# MotorCell.net
KiCad netlist of a schematic drawn in Altium Designer
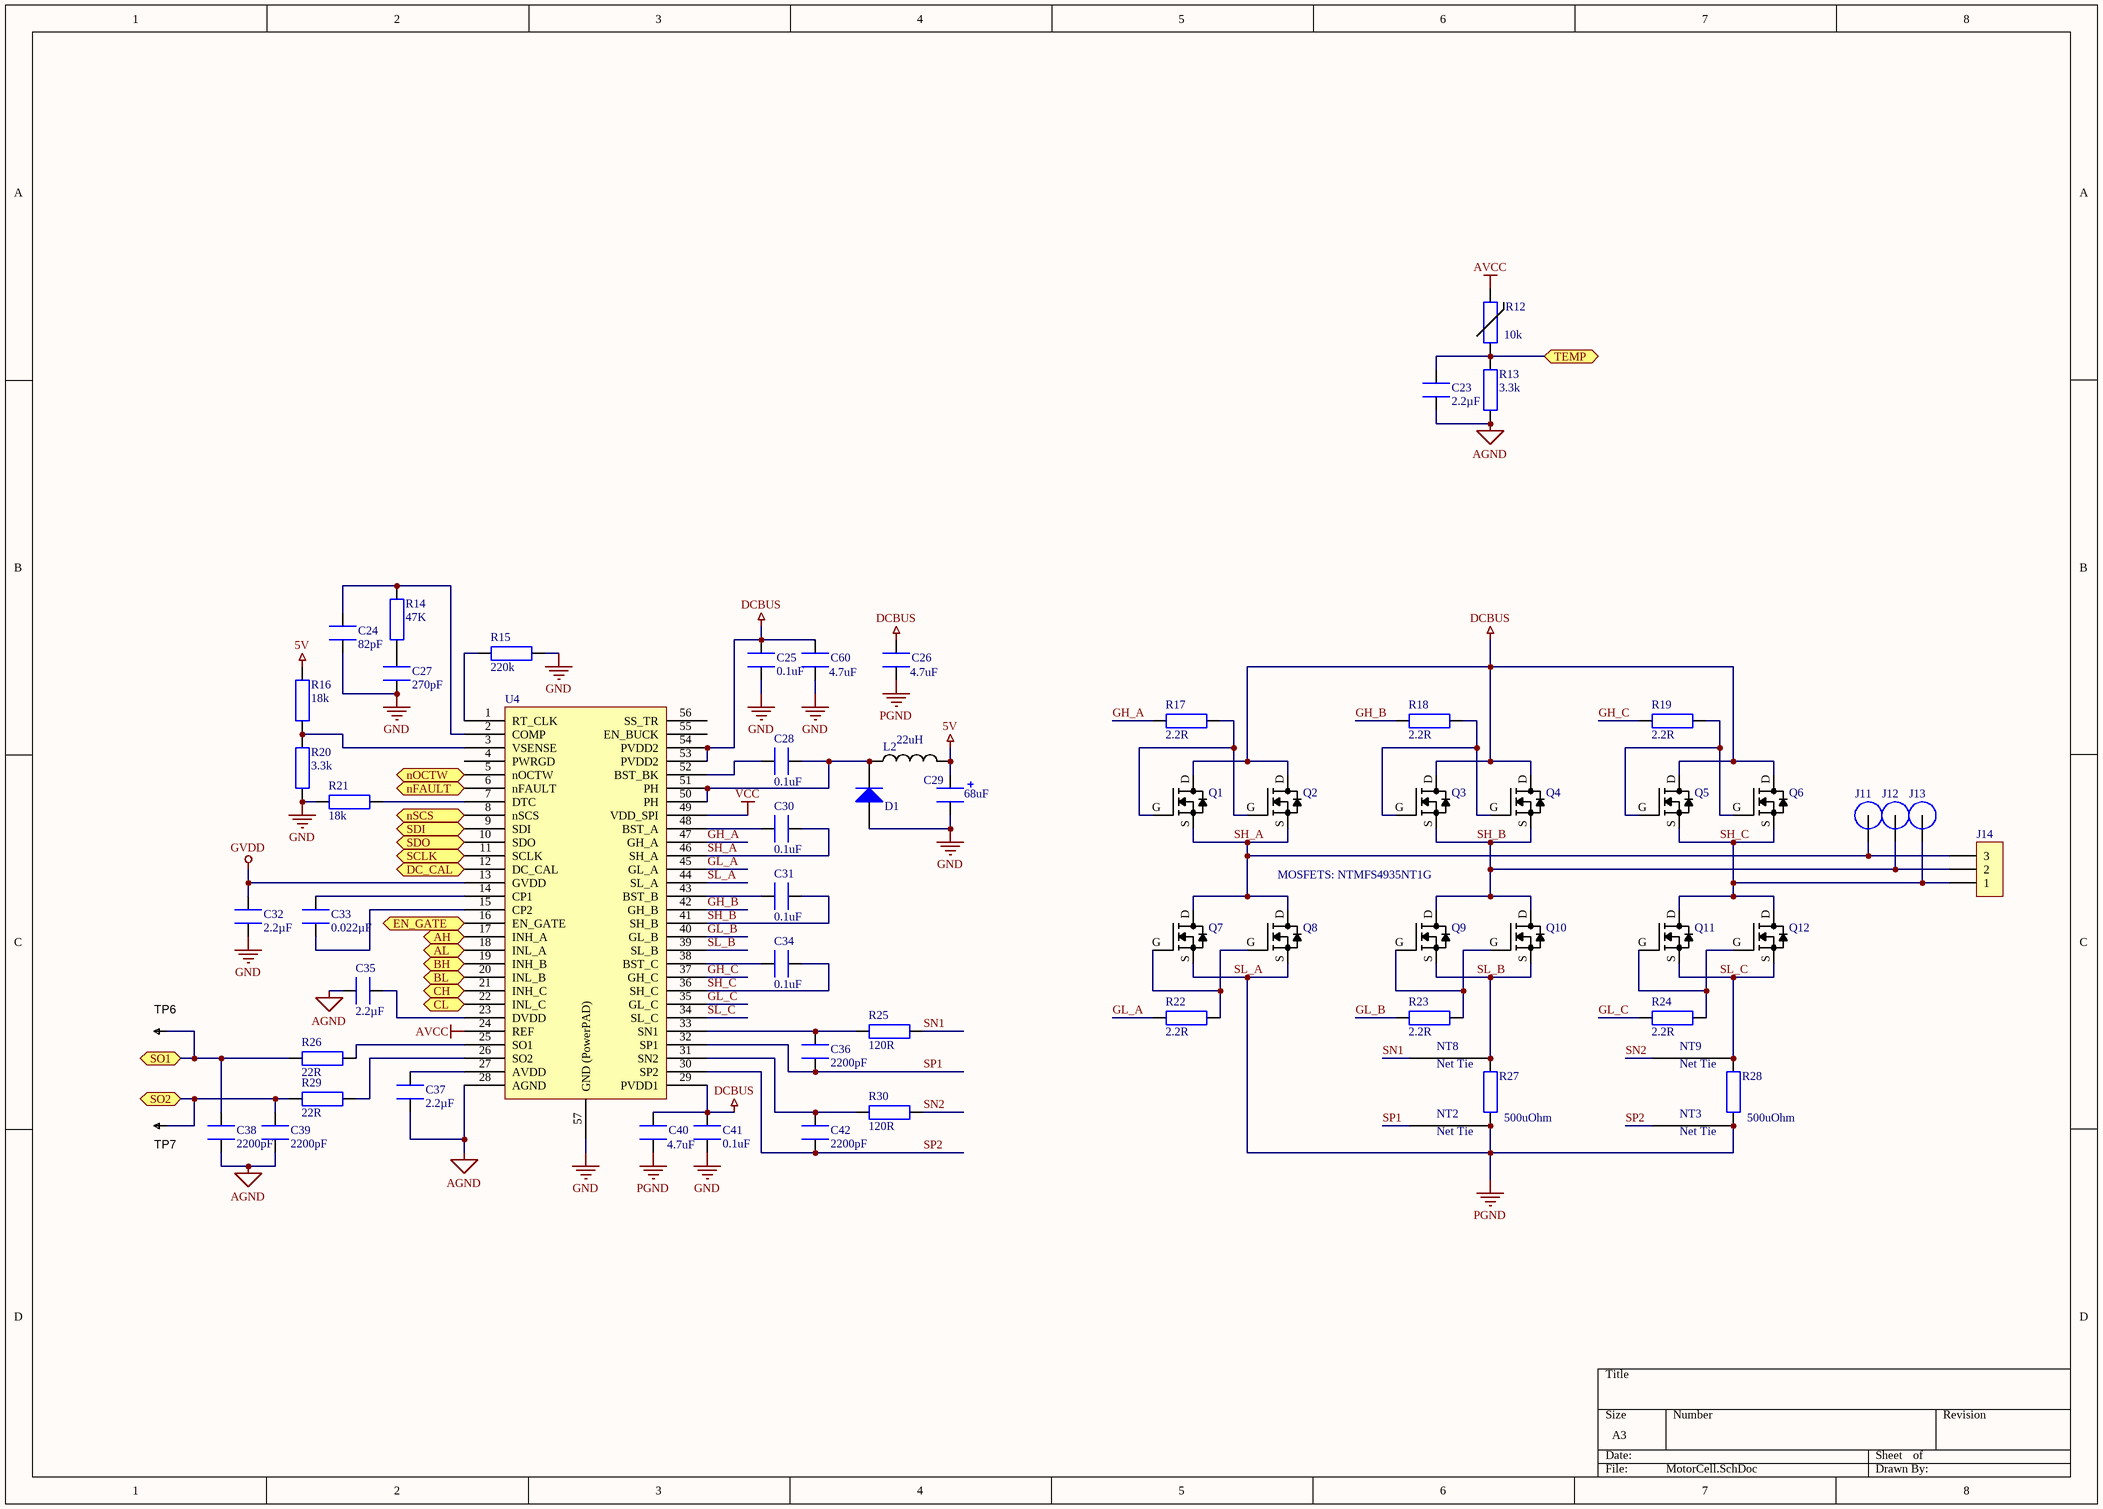
[diagram p0: MotorCell.SchDoc]

(export (version "E")
  (design (tool "Eeschema 10.0.6"))
  (components
    (comp (ref "C23")
      (value "2.2µF")
      (footprint "CAPC1608X09L")
      (description "CAP CER 2.2UF 16V X5R 0603")
      (fields
        (field (name "MANUFACTURER") "Murata Electronics North America")
        (field (name "MANUFACTURER PART NUMBER") "GRM188R61C225KE15D")
      )
      (libsource (lib "CustomComponents") (part "GRM188R61C225KE15D"))
    )
    (comp (ref "C24")
      (value "82pF")
      (footprint "CAPC1608X09L")
      (description "CAP CER 82PF 100V NP0 0603")
      (fields
        (field (name "MANUFACTURER") "Murata Electronics North America")
        (field (name "MANUFACTURER PART NUMBER") "GRM1885C2A820JA01D")
      )
      (libsource (lib "CustomComponents") (part "GRM1885C2A820JA01D"))
    )
    (comp (ref "C25")
      (value "0.1uF")
      (footprint "CAPC1608X09L")
      (description "CAP CER 0.1UF 50V X7R 0603")
      (fields
        (field (name "MANUFACTURER") "Murata Electronics North America")
        (field (name "MANUFACTURER PART NUMBER") "GRM188R71H104KA93D")
      )
      (libsource (lib "CustomComponents") (part "GRM188R71H104KA93D"))
    )
    (comp (ref "C26")
      (value "4.7uF")
      (footprint "CAPC2012X09N")
      (description "CAP CER 4.7UF 35V X5R 0805")
      (fields
        (field (name "MANUFACTURER") "Murata Electronics North America")
        (field (name "TOLERANCE") "?0%")
      )
      (libsource (lib "CustomComponents") (part "GRM219R6YA475KA73D"))
    )
    (comp (ref "C27")
      (value "270pF")
      (footprint "CAPC1608X09L")
      (description "CAP CER 270PF 50V NP0 0603")
      (fields
        (field (name "MANUFACTURER") "Murata Electronics North America")
        (field (name "MANUFACTURER PART NUMBER") "GRM1885C1H271JA01D")
      )
      (libsource (lib "CustomComponents") (part "GRM1885C1H271JA01D"))
    )
    (comp (ref "C28")
      (value "0.1uF")
      (footprint "CAPC1608X09L")
      (description "CAP CER 0.1UF 50V X7R 0603")
      (fields
        (field (name "MANUFACTURER") "Murata Electronics North America")
        (field (name "MANUFACTURER PART NUMBER") "GRM188R71H104KA93D")
      )
      (libsource (lib "CustomComponents") (part "GRM188R71H104KA93D"))
    )
    (comp (ref "C29")
      (value "68uF")
      (footprint "CAPCP6032X28N")
      (description "CAP TANT 68UF 16V 20% 2312 250mOhm")
      (fields (field (name "MANUFACTURER") "KEMET") (field (name "TOLERANCE") "?0%"))
      (libsource (lib "CustomComponents") (part "T495C686M016ATE250"))
    )
    (comp (ref "C30")
      (value "0.1uF")
      (footprint "CAPC1608X09L")
      (description "CAP CER 0.1UF 50V X7R 0603")
      (fields
        (field (name "MANUFACTURER") "Murata Electronics North America")
        (field (name "MANUFACTURER PART NUMBER") "GRM188R71H104KA93D")
      )
      (libsource (lib "CustomComponents") (part "GRM188R71H104KA93D"))
    )
    (comp (ref "C31")
      (value "0.1uF")
      (footprint "CAPC1608X09L")
      (description "CAP CER 0.1UF 50V X7R 0603")
      (fields
        (field (name "MANUFACTURER") "Murata Electronics North America")
        (field (name "MANUFACTURER PART NUMBER") "GRM188R71H104KA93D")
      )
      (libsource (lib "CustomComponents") (part "GRM188R71H104KA93D"))
    )
    (comp (ref "C32")
      (value "2.2µF")
      (footprint "CAPC1608X09L")
      (description "CAP CER 2.2UF 16V X5R 0603")
      (fields
        (field (name "MANUFACTURER") "Murata Electronics North America")
        (field (name "MANUFACTURER PART NUMBER") "GRM188R61C225KE15D")
      )
      (libsource (lib "CustomComponents") (part "GRM188R61C225KE15D"))
    )
    (comp (ref "C33")
      (value "0.022µF")
      (footprint "CAPC1608X09L")
      (description "CAP CER 0.022UF 50V X7R 0603")
      (fields
        (field (name "MANUFACTURER") "Murata Electronics North America")
        (field (name "MANUFACTURER PART NUMBER") "GRM188R71H223KA01D")
      )
      (libsource (lib "CustomComponents") (part "GRM188R71H223KA01D"))
    )
    (comp (ref "C34")
      (value "0.1uF")
      (footprint "CAPC1608X09L")
      (description "CAP CER 0.1UF 50V X7R 0603")
      (fields
        (field (name "MANUFACTURER") "Murata Electronics North America")
        (field (name "MANUFACTURER PART NUMBER") "GRM188R71H104KA93D")
      )
      (libsource (lib "CustomComponents") (part "GRM188R71H104KA93D"))
    )
    (comp (ref "C35")
      (value "2.2µF")
      (footprint "CAPC1608X09L")
      (description "CAP CER 2.2UF 16V X5R 0603")
      (fields
        (field (name "MANUFACTURER") "Murata Electronics North America")
        (field (name "MANUFACTURER PART NUMBER") "GRM188R61C225KE15D")
      )
      (libsource (lib "CustomComponents") (part "GRM188R61C225KE15D"))
    )
    (comp (ref "C36")
      (value "2200pF")
      (footprint "CAPC1608X09L")
      (description "CAP CER 2200PF 50V NP0 0603")
      (fields
        (field (name "MANUFACTURER") "Murata Electronics North America")
        (field (name "TOLERANCE") "?%")
      )
      (libsource (lib "CustomComponents") (part "GRM1885C1H222JA01D"))
    )
    (comp (ref "C37")
      (value "2.2µF")
      (footprint "CAPC1608X09L")
      (description "CAP CER 2.2UF 16V X5R 0603")
      (fields
        (field (name "MANUFACTURER") "Murata Electronics North America")
        (field (name "MANUFACTURER PART NUMBER") "GRM188R61C225KE15D")
      )
      (libsource (lib "CustomComponents") (part "GRM188R61C225KE15D"))
    )
    (comp (ref "C38")
      (value "2200pF")
      (footprint "CAPC1608X09L")
      (description "CAP CER 2200PF 50V NP0 0603")
      (fields
        (field (name "MANUFACTURER") "Murata Electronics North America")
        (field (name "TOLERANCE") "?%")
      )
      (libsource (lib "CustomComponents") (part "GRM1885C1H222JA01D"))
    )
    (comp (ref "C39")
      (value "2200pF")
      (footprint "CAPC1608X09L")
      (description "CAP CER 2200PF 50V NP0 0603")
      (fields
        (field (name "MANUFACTURER") "Murata Electronics North America")
        (field (name "TOLERANCE") "?%")
      )
      (libsource (lib "CustomComponents") (part "GRM1885C1H222JA01D"))
    )
    (comp (ref "C40")
      (value "4.7uF")
      (footprint "CAPC2012X09N")
      (description "CAP CER 4.7UF 35V X5R 0805")
      (fields
        (field (name "MANUFACTURER") "Murata Electronics North America")
        (field (name "TOLERANCE") "?0%")
      )
      (libsource (lib "CustomComponents") (part "GRM219R6YA475KA73D"))
    )
    (comp (ref "C41")
      (value "0.1uF")
      (footprint "CAPC1608X09L")
      (description "CAP CER 0.1UF 50V X7R 0603")
      (fields
        (field (name "MANUFACTURER") "Murata Electronics North America")
        (field (name "MANUFACTURER PART NUMBER") "GRM188R71H104KA93D")
      )
      (libsource (lib "CustomComponents") (part "GRM188R71H104KA93D"))
    )
    (comp (ref "C42")
      (value "2200pF")
      (footprint "CAPC1608X09L")
      (description "CAP CER 2200PF 50V NP0 0603")
      (fields
        (field (name "MANUFACTURER") "Murata Electronics North America")
        (field (name "TOLERANCE") "?%")
      )
      (libsource (lib "CustomComponents") (part "GRM1885C1H222JA01D"))
    )
    (comp (ref "C60")
      (value "4.7uF")
      (footprint "CAPC2012X09N")
      (description "CAP CER 4.7UF 35V X5R 0805")
      (fields
        (field (name "MANUFACTURER") "Murata Electronics North America")
        (field (name "TOLERANCE") "?0%")
      )
      (libsource (lib "CustomComponents") (part "GRM219R6YA475KA73D"))
    )
    (comp (ref "D1")
      (value "~")
      (footprint "DIOM2717X10N")
      (description "Rectifier Diode, Single, 40 V, 1 A, SOD-123FL, 2, 550 mV")
      (libsource (lib "CustomComponents") (part "MBR140SFT1G"))
    )
    (comp (ref "J11")
      (value "~")
      (footprint "M3 Spade Hole")
      (description "M3 Spade Terminal")
      (libsource (lib "CustomComponents") (part "M3 Spade Terminal"))
    )
    (comp (ref "J12")
      (value "~")
      (footprint "M3 Spade Hole")
      (description "M3 Spade Terminal")
      (libsource (lib "CustomComponents") (part "M3 Spade Terminal"))
    )
    (comp (ref "J13")
      (value "~")
      (footprint "M3 Spade Hole")
      (description "M3 Spade Terminal")
      (libsource (lib "CustomComponents") (part "M3 Spade Terminal"))
    )
    (comp (ref "J14")
      (value "1704936")
      (footprint "1704936")
      (description "CONN TERM BLOCK 3POS 7.62MM")
      (fields (field (name "MANUFACTURER") "Phoenix Contact") (field (name "VOLTAGE") "300V"))
      (libsource (lib "CustomComponents") (part "1704936"))
    )
    (comp (ref "L2")
      (value "22uH")
      (footprint "INDC6060X28N")
      (description "INDUCTOR 22UH 1.4A 175.5 MOHM")
      (libsource (lib "CustomComponents") (part "NR6028T220M"))
    )
    (comp (ref "NT2")
      (value "0.25mm")
      (footprint "NetTie_0.25mm")
      (libsource (lib "CustomComponents") (part "NetTie_0.25mm"))
    )
    (comp (ref "NT3")
      (value "0.25mm")
      (footprint "NetTie_0.25mm")
      (libsource (lib "CustomComponents") (part "NetTie_0.25mm"))
    )
    (comp (ref "NT8")
      (value "0.25mm")
      (footprint "NetTie_0.25mm")
      (libsource (lib "CustomComponents") (part "NetTie_0.25mm"))
    )
    (comp (ref "NT9")
      (value "0.25mm")
      (footprint "NetTie_0.25mm")
      (libsource (lib "CustomComponents") (part "NetTie_0.25mm"))
    )
    (comp (ref "Q1")
      (value "~")
      (footprint "SO8FL")
      (description "MOSFET N-CH 30V 13A SO8FL")
      (fields
        (field (name "MANUFACTURER") "ON Semiconductor")
        (field (name "MANUFACTURER PART NUMBER") "NTMFS4935NT1G")
      )
      (libsource (lib "CustomComponents") (part "NTMFS4935NT1G"))
    )
    (comp (ref "Q2")
      (value "FILL_FOOTPRINT")
      (footprint "SO8FL_FILL")
      (description "MOSFET N-CH 30V 13A SO8FL")
      (fields
        (field (name "MANUFACTURER") "ON Semiconductor")
        (field (name "MANUFACTURER PART NUMBER") "NTMFS4935NT1G")
      )
      (libsource (lib "CustomComponents") (part "NTMFS4935NT1G"))
    )
    (comp (ref "Q3")
      (value "~")
      (footprint "SO8FL")
      (description "MOSFET N-CH 30V 13A SO8FL")
      (fields
        (field (name "MANUFACTURER") "ON Semiconductor")
        (field (name "MANUFACTURER PART NUMBER") "NTMFS4935NT1G")
      )
      (libsource (lib "CustomComponents") (part "NTMFS4935NT1G"))
    )
    (comp (ref "Q4")
      (value "FILL_FOOTPRINT")
      (footprint "SO8FL_FILL")
      (description "MOSFET N-CH 30V 13A SO8FL")
      (fields
        (field (name "MANUFACTURER") "ON Semiconductor")
        (field (name "MANUFACTURER PART NUMBER") "NTMFS4935NT1G")
      )
      (libsource (lib "CustomComponents") (part "NTMFS4935NT1G"))
    )
    (comp (ref "Q5")
      (value "~")
      (footprint "SO8FL")
      (description "MOSFET N-CH 30V 13A SO8FL")
      (fields
        (field (name "MANUFACTURER") "ON Semiconductor")
        (field (name "MANUFACTURER PART NUMBER") "NTMFS4935NT1G")
      )
      (libsource (lib "CustomComponents") (part "NTMFS4935NT1G"))
    )
    (comp (ref "Q6")
      (value "FILL_FOOTPRINT")
      (footprint "SO8FL_FILL")
      (description "MOSFET N-CH 30V 13A SO8FL")
      (fields
        (field (name "MANUFACTURER") "ON Semiconductor")
        (field (name "MANUFACTURER PART NUMBER") "NTMFS4935NT1G")
      )
      (libsource (lib "CustomComponents") (part "NTMFS4935NT1G"))
    )
    (comp (ref "Q7")
      (value "~")
      (footprint "SO8FL")
      (description "MOSFET N-CH 30V 13A SO8FL")
      (fields
        (field (name "MANUFACTURER") "ON Semiconductor")
        (field (name "MANUFACTURER PART NUMBER") "NTMFS4935NT1G")
      )
      (libsource (lib "CustomComponents") (part "NTMFS4935NT1G"))
    )
    (comp (ref "Q8")
      (value "~")
      (footprint "SO8FL")
      (description "MOSFET N-CH 30V 13A SO8FL")
      (fields
        (field (name "MANUFACTURER") "ON Semiconductor")
        (field (name "MANUFACTURER PART NUMBER") "NTMFS4935NT1G")
      )
      (libsource (lib "CustomComponents") (part "NTMFS4935NT1G"))
    )
    (comp (ref "Q9")
      (value "~")
      (footprint "SO8FL")
      (description "MOSFET N-CH 30V 13A SO8FL")
      (fields
        (field (name "MANUFACTURER") "ON Semiconductor")
        (field (name "MANUFACTURER PART NUMBER") "NTMFS4935NT1G")
      )
      (libsource (lib "CustomComponents") (part "NTMFS4935NT1G"))
    )
    (comp (ref "Q10")
      (value "~")
      (footprint "SO8FL")
      (description "MOSFET N-CH 30V 13A SO8FL")
      (fields
        (field (name "MANUFACTURER") "ON Semiconductor")
        (field (name "MANUFACTURER PART NUMBER") "NTMFS4935NT1G")
      )
      (libsource (lib "CustomComponents") (part "NTMFS4935NT1G"))
    )
    (comp (ref "Q11")
      (value "~")
      (footprint "SO8FL")
      (description "MOSFET N-CH 30V 13A SO8FL")
      (fields
        (field (name "MANUFACTURER") "ON Semiconductor")
        (field (name "MANUFACTURER PART NUMBER") "NTMFS4935NT1G")
      )
      (libsource (lib "CustomComponents") (part "NTMFS4935NT1G"))
    )
    (comp (ref "Q12")
      (value "~")
      (footprint "SO8FL")
      (description "MOSFET N-CH 30V 13A SO8FL")
      (fields
        (field (name "MANUFACTURER") "ON Semiconductor")
        (field (name "MANUFACTURER PART NUMBER") "NTMFS4935NT1G")
      )
      (libsource (lib "CustomComponents") (part "NTMFS4935NT1G"))
    )
    (comp (ref "R12")
      (value "10k")
      (footprint "RESC1005X40N")
      (description "THERMISTOR 10K OHM NTC 0402 SMD")
      (libsource (lib "CustomComponents") (part "NCP15XH103F03RC"))
    )
    (comp (ref "R13")
      (value "3.3k")
      (footprint "RESC1608X55N")
      (description "RES SMD 3.3K OHM 1% 1/10W 0603")
      (fields
        (field (name "MANUFACTURER") "Yageo")
        (field (name "MANUFACTURER PART NUMBER") "RC0603FR-073K3L")
      )
      (libsource (lib "CustomComponents") (part "RC0603FR-073K3L"))
    )
    (comp (ref "R14")
      (value "47K")
      (footprint "RESC1608X55N")
      (description "RES SMD 47K OHM 1% 1/10W 0603")
      (fields
        (field (name "MANUFACTURER") "Yageo")
        (field (name "MANUFACTURER PART NUMBER") "RC0603FR-0747KL")
      )
      (libsource (lib "CustomComponents") (part "RC0603FR-0747KL"))
    )
    (comp (ref "R15")
      (value "220k")
      (footprint "RESC1608X55N")
      (description "RES SMD 220K OHM 1% 1/10W 0603")
      (fields
        (field (name "MANUFACTURER") "Yageo")
        (field (name "MANUFACTURER PART NUMBER") "RC0603FR-07220KL")
      )
      (libsource (lib "CustomComponents") (part "RC0603FR-07220KL"))
    )
    (comp (ref "R16")
      (value "18k")
      (footprint "RESC1608X55N")
      (description "RES SMD 18K OHM 1% 1/10W 0603")
      (fields
        (field (name "MANUFACTURER") "Yageo")
        (field (name "MANUFACTURER PART NUMBER") "RC0603FR-0718KL")
      )
      (libsource (lib "CustomComponents") (part "RC0603FR-0718KL"))
    )
    (comp (ref "R17")
      (value "2.2R")
      (footprint "RESC1608X55N")
      (description "RES SMD 2.2 OHM 1% 1/10W 0603")
      (fields
        (field (name "MANUFACTURER") "Yageo")
        (field (name "MANUFACTURER PART NUMBER") "RC0603FR-072R2L")
      )
      (libsource (lib "CustomComponents") (part "RC0603FR-072R2L"))
    )
    (comp (ref "R18")
      (value "2.2R")
      (footprint "RESC1608X55N")
      (description "RES SMD 2.2 OHM 1% 1/10W 0603")
      (fields
        (field (name "MANUFACTURER") "Yageo")
        (field (name "MANUFACTURER PART NUMBER") "RC0603FR-072R2L")
      )
      (libsource (lib "CustomComponents") (part "RC0603FR-072R2L"))
    )
    (comp (ref "R19")
      (value "2.2R")
      (footprint "RESC1608X55N")
      (description "RES SMD 2.2 OHM 1% 1/10W 0603")
      (fields
        (field (name "MANUFACTURER") "Yageo")
        (field (name "MANUFACTURER PART NUMBER") "RC0603FR-072R2L")
      )
      (libsource (lib "CustomComponents") (part "RC0603FR-072R2L"))
    )
    (comp (ref "R20")
      (value "3.3k")
      (footprint "RESC1608X55N")
      (description "RES SMD 3.3K OHM 1% 1/10W 0603")
      (fields
        (field (name "MANUFACTURER") "Yageo")
        (field (name "MANUFACTURER PART NUMBER") "RC0603FR-073K3L")
      )
      (libsource (lib "CustomComponents") (part "RC0603FR-073K3L"))
    )
    (comp (ref "R21")
      (value "18k")
      (footprint "RESC1608X55N")
      (description "RES SMD 18K OHM 1% 1/10W 0603")
      (fields
        (field (name "MANUFACTURER") "Yageo")
        (field (name "MANUFACTURER PART NUMBER") "RC0603FR-0718KL")
      )
      (libsource (lib "CustomComponents") (part "RC0603FR-0718KL"))
    )
    (comp (ref "R22")
      (value "2.2R")
      (footprint "RESC1608X55N")
      (description "RES SMD 2.2 OHM 1% 1/10W 0603")
      (fields
        (field (name "MANUFACTURER") "Yageo")
        (field (name "MANUFACTURER PART NUMBER") "RC0603FR-072R2L")
      )
      (libsource (lib "CustomComponents") (part "RC0603FR-072R2L"))
    )
    (comp (ref "R23")
      (value "2.2R")
      (footprint "RESC1608X55N")
      (description "RES SMD 2.2 OHM 1% 1/10W 0603")
      (fields
        (field (name "MANUFACTURER") "Yageo")
        (field (name "MANUFACTURER PART NUMBER") "RC0603FR-072R2L")
      )
      (libsource (lib "CustomComponents") (part "RC0603FR-072R2L"))
    )
    (comp (ref "R24")
      (value "2.2R")
      (footprint "RESC1608X55N")
      (description "RES SMD 2.2 OHM 1% 1/10W 0603")
      (fields
        (field (name "MANUFACTURER") "Yageo")
        (field (name "MANUFACTURER PART NUMBER") "RC0603FR-072R2L")
      )
      (libsource (lib "CustomComponents") (part "RC0603FR-072R2L"))
    )
    (comp (ref "R25")
      (value "120R")
      (footprint "RESC1608X55N")
      (description "RES SMD 120 OHM 1% 1/10W 0603")
      (fields
        (field (name "MANUFACTURER") "Yageo")
        (field (name "MANUFACTURER PART NUMBER") "RC0603FR-07120RL")
      )
      (libsource (lib "CustomComponents") (part "RC0603FR-07120RL"))
    )
    (comp (ref "R26")
      (value "22R")
      (footprint "RESC1608X55N")
      (description "RES SMD 22 OHM 1% 1/10W 0603")
      (fields
        (field (name "MANUFACTURER") "Yageo")
        (field (name "MANUFACTURER PART NUMBER") "RC0603FR-0722RL")
      )
      (libsource (lib "CustomComponents") (part "RC0603FR-0722RL"))
    )
    (comp (ref "R27")
      (value "500uOhm")
      (footprint "RESC6432X09N")
      (description "RES SMD 0.0005 OHM 1% 3W 2512")
      (fields (field (name "MANUFACTURER") "Riedon") (field (name "TOLERANCE") "?%"))
      (libsource (lib "CustomComponents") (part "CSR2512C0R0005F"))
    )
    (comp (ref "R28")
      (value "500uOhm")
      (footprint "RESC6432X09N")
      (description "RES SMD 0.0005 OHM 1% 3W 2512")
      (fields (field (name "MANUFACTURER") "Riedon") (field (name "TOLERANCE") "?%"))
      (libsource (lib "CustomComponents") (part "CSR2512C0R0005F"))
    )
    (comp (ref "R29")
      (value "22R")
      (footprint "RESC1608X55N")
      (description "RES SMD 22 OHM 1% 1/10W 0603")
      (fields
        (field (name "MANUFACTURER") "Yageo")
        (field (name "MANUFACTURER PART NUMBER") "RC0603FR-0722RL")
      )
      (libsource (lib "CustomComponents") (part "RC0603FR-0722RL"))
    )
    (comp (ref "R30")
      (value "120R")
      (footprint "RESC1608X55N")
      (description "RES SMD 120 OHM 1% 1/10W 0603")
      (fields
        (field (name "MANUFACTURER") "Yageo")
        (field (name "MANUFACTURER PART NUMBER") "RC0603FR-07120RL")
      )
      (libsource (lib "CustomComponents") (part "RC0603FR-07120RL"))
    )
    (comp (ref "TP6")
      (value "TESTPOINT")
      (footprint "TP-R30")
      (description "SMD test pin")
      (libsource (lib "PBL - Test Points") (part "TESTPOINT"))
    )
    (comp (ref "TP7")
      (value "TESTPOINT")
      (footprint "TP-R30")
      (description "SMD test pin")
      (libsource (lib "PBL - Test Points") (part "TESTPOINT"))
    )
    (comp (ref "U4")
      (value "~")
      (footprint "TSSOP50P810X120_HS-57N")
      (description "MOTOR DRIVER, 3PH, 56HTSSOP")
      (libsource (lib "CustomComponents") (part "DRV8301"))
    )
  )
  (nets
    (net (code "1") (name "/AH") (class "Default")
      (node (ref "U4") (pin "17") (pinfunction "INH_A_17") (pintype "passive"))
    )
    (net (code "2") (name "/AL") (class "Default")
      (node (ref "U4") (pin "18") (pinfunction "INL_A_18") (pintype "passive"))
    )
    (net (code "3") (name "/BH") (class "Default")
      (node (ref "U4") (pin "19") (pinfunction "INH_B_19") (pintype "passive"))
    )
    (net (code "4") (name "/BL") (class "Default")
      (node (ref "U4") (pin "20") (pinfunction "INL_B_20") (pintype "passive"))
    )
    (net (code "5") (name "/CH") (class "Default")
      (node (ref "U4") (pin "21") (pinfunction "INH_C_21") (pintype "passive"))
    )
    (net (code "6") (name "/CL") (class "Default")
      (node (ref "U4") (pin "22") (pinfunction "INL_C_22") (pintype "passive"))
    )
    (net (code "7") (name "/DC_CAL") (class "Default")
      (node (ref "U4") (pin "12") (pinfunction "DC_CAL_12") (pintype "passive"))
    )
    (net (code "8") (name "/EN_GATE") (class "Default")
      (node (ref "U4") (pin "16") (pinfunction "EN_GATE_16") (pintype "passive"))
    )
    (net (code "9") (name "/GH_A") (class "Default")
      (node (ref "R17") (pin "2") (pinfunction "0_2") (pintype "passive"))
      (node (ref "U4") (pin "47") (pinfunction "GH_A_47") (pintype "passive"))
    )
    (net (code "10") (name "/GH_B") (class "Default")
      (node (ref "R18") (pin "2") (pinfunction "0_2") (pintype "passive"))
      (node (ref "U4") (pin "42") (pinfunction "GH_B_42") (pintype "passive"))
    )
    (net (code "11") (name "/GH_C") (class "Default")
      (node (ref "R19") (pin "2") (pinfunction "0_2") (pintype "passive"))
      (node (ref "U4") (pin "37") (pinfunction "GH_C_37") (pintype "passive"))
    )
    (net (code "12") (name "/GL_A") (class "Default")
      (node (ref "R22") (pin "2") (pinfunction "0_2") (pintype "passive"))
      (node (ref "U4") (pin "45") (pinfunction "GL_A_45") (pintype "passive"))
    )
    (net (code "13") (name "/GL_B") (class "Default")
      (node (ref "R23") (pin "2") (pinfunction "0_2") (pintype "passive"))
      (node (ref "U4") (pin "40") (pinfunction "GL_B_40") (pintype "passive"))
    )
    (net (code "14") (name "/GL_C") (class "Default")
      (node (ref "R24") (pin "2") (pinfunction "0_2") (pintype "passive"))
      (node (ref "U4") (pin "35") (pinfunction "GL_C_35") (pintype "passive"))
    )
    (net (code "15") (name "/SCLK") (class "Default")
      (node (ref "U4") (pin "11") (pinfunction "SCLK_11") (pintype "passive"))
    )
    (net (code "16") (name "/SDI") (class "Default")
      (node (ref "U4") (pin "9") (pinfunction "SDI_9") (pintype "passive"))
    )
    (net (code "17") (name "/SDO") (class "Default")
      (node (ref "U4") (pin "10") (pinfunction "SDO_10") (pintype "passive"))
    )
    (net (code "18") (name "/SH_A") (class "Default")
      (node (ref "C30") (pin "1") (pinfunction "1_1") (pintype "passive"))
      (node (ref "J11") (pin "1") (pinfunction "1_1") (pintype "passive"))
      (node (ref "J14") (pin "3") (pinfunction "3_3") (pintype "passive"))
      (node (ref "Q1") (pin "S") (pinfunction "S_S") (pintype "passive"))
      (node (ref "Q2") (pin "S") (pinfunction "S_S") (pintype "passive"))
      (node (ref "Q7") (pin "D") (pinfunction "D_D") (pintype "passive"))
      (node (ref "Q8") (pin "D") (pinfunction "D_D") (pintype "passive"))
      (node (ref "U4") (pin "46") (pinfunction "SH_A_46") (pintype "passive"))
    )
    (net (code "19") (name "/SH_B") (class "Default")
      (node (ref "C31") (pin "1") (pinfunction "1_1") (pintype "passive"))
      (node (ref "J12") (pin "1") (pinfunction "1_1") (pintype "passive"))
      (node (ref "J14") (pin "2") (pinfunction "2_2") (pintype "passive"))
      (node (ref "Q10") (pin "D") (pinfunction "D_D") (pintype "passive"))
      (node (ref "Q3") (pin "S") (pinfunction "S_S") (pintype "passive"))
      (node (ref "Q4") (pin "S") (pinfunction "S_S") (pintype "passive"))
      (node (ref "Q9") (pin "D") (pinfunction "D_D") (pintype "passive"))
      (node (ref "U4") (pin "41") (pinfunction "SH_B_41") (pintype "passive"))
    )
    (net (code "20") (name "/SH_C") (class "Default")
      (node (ref "C34") (pin "1") (pinfunction "1_1") (pintype "passive"))
      (node (ref "J13") (pin "1") (pinfunction "1_1") (pintype "passive"))
      (node (ref "J14") (pin "1") (pinfunction "1_1") (pintype "passive"))
      (node (ref "Q11") (pin "D") (pinfunction "D_D") (pintype "passive"))
      (node (ref "Q12") (pin "D") (pinfunction "D_D") (pintype "passive"))
      (node (ref "Q5") (pin "S") (pinfunction "S_S") (pintype "passive"))
      (node (ref "Q6") (pin "S") (pinfunction "S_S") (pintype "passive"))
      (node (ref "U4") (pin "36") (pinfunction "SH_C_36") (pintype "passive"))
    )
    (net (code "21") (name "/SL_B") (class "Default")
      (node (ref "NT8") (pin "2") (pintype "passive"))
      (node (ref "Q10") (pin "S") (pinfunction "S_S") (pintype "passive"))
      (node (ref "Q9") (pin "S") (pinfunction "S_S") (pintype "passive"))
      (node (ref "R27") (pin "2") (pinfunction "0_2") (pintype "passive"))
      (node (ref "U4") (pin "39") (pinfunction "SL_B_39") (pintype "passive"))
    )
    (net (code "22") (name "/SL_C") (class "Default")
      (node (ref "NT9") (pin "2") (pintype "passive"))
      (node (ref "Q11") (pin "S") (pinfunction "S_S") (pintype "passive"))
      (node (ref "Q12") (pin "S") (pinfunction "S_S") (pintype "passive"))
      (node (ref "R28") (pin "2") (pinfunction "0_2") (pintype "passive"))
      (node (ref "U4") (pin "34") (pinfunction "SL_C_34") (pintype "passive"))
    )
    (net (code "23") (name "/SN1") (class "Default")
      (node (ref "NT8") (pin "1") (pintype "passive"))
      (node (ref "R25") (pin "1") (pinfunction "0_1") (pintype "passive"))
    )
    (net (code "24") (name "/SN2") (class "Default")
      (node (ref "NT9") (pin "1") (pintype "passive"))
      (node (ref "R30") (pin "1") (pinfunction "0_1") (pintype "passive"))
    )
    (net (code "25") (name "/SO1") (class "Default")
      (node (ref "C38") (pin "1") (pinfunction "1_1") (pintype "passive"))
      (node (ref "R26") (pin "2") (pinfunction "0_2") (pintype "passive"))
      (node (ref "TP6") (pin "1") (pintype "passive"))
    )
    (net (code "26") (name "/SO2") (class "Default")
      (node (ref "C39") (pin "1") (pinfunction "1_1") (pintype "passive"))
      (node (ref "R29") (pin "2") (pinfunction "0_2") (pintype "passive"))
      (node (ref "TP7") (pin "1") (pintype "passive"))
    )
    (net (code "27") (name "/SP1") (class "Default")
      (node (ref "C36") (pin "2") (pinfunction "2_2") (pintype "passive"))
      (node (ref "NT2") (pin "1") (pintype "passive"))
      (node (ref "U4") (pin "32") (pinfunction "SP1_32") (pintype "passive"))
    )
    (net (code "28") (name "/SP2") (class "Default")
      (node (ref "C42") (pin "2") (pinfunction "2_2") (pintype "passive"))
      (node (ref "NT3") (pin "1") (pintype "passive"))
      (node (ref "U4") (pin "30") (pinfunction "SP2_30") (pintype "passive"))
    )
    (net (code "29") (name "/TEMP") (class "Default")
      (node (ref "C23") (pin "2") (pinfunction "2_2") (pintype "passive"))
      (node (ref "R12") (pin "1") (pinfunction "0_1") (pintype "passive"))
      (node (ref "R13") (pin "1") (pinfunction "0_1") (pintype "passive"))
    )
    (net (code "30") (name "/nFAULT") (class "Default")
      (node (ref "U4") (pin "6") (pinfunction "nFAULT_6") (pintype "passive"))
    )
    (net (code "31") (name "/nOCTW") (class "Default")
      (node (ref "U4") (pin "5") (pinfunction "nOCTW_5") (pintype "passive"))
    )
    (net (code "32") (name "/nSCS") (class "Default")
      (node (ref "U4") (pin "8") (pinfunction "nSCS_8") (pintype "passive"))
    )
    (net (code "33") (name "5V") (class "Default")
      (node (ref "C29") (pin "1") (pinfunction "1_1") (pintype "passive"))
      (node (ref "L2") (pin "2") (pinfunction "2_2") (pintype "passive"))
      (node (ref "R16") (pin "1") (pinfunction "0_1") (pintype "passive"))
    )
    (net (code "34") (name "AGND") (class "Default")
      (node (ref "C23") (pin "1") (pinfunction "1_1") (pintype "passive"))
      (node (ref "C35") (pin "1") (pinfunction "1_1") (pintype "passive"))
      (node (ref "C37") (pin "1") (pinfunction "1_1") (pintype "passive"))
      (node (ref "C38") (pin "2") (pinfunction "2_2") (pintype "passive"))
      (node (ref "C39") (pin "2") (pinfunction "2_2") (pintype "passive"))
      (node (ref "R13") (pin "2") (pinfunction "0_2") (pintype "passive"))
      (node (ref "U4") (pin "28") (pinfunction "AGND_28") (pintype "passive"))
    )
    (net (code "35") (name "AVCC") (class "Default")
      (node (ref "R12") (pin "2") (pinfunction "0_2") (pintype "passive"))
      (node (ref "U4") (pin "24") (pinfunction "REF_24") (pintype "passive"))
    )
    (net (code "36") (name "DCBUS") (class "Default")
      (node (ref "C25") (pin "1") (pinfunction "1_1") (pintype "passive"))
      (node (ref "C26") (pin "2") (pinfunction "2_2") (pintype "passive"))
      (node (ref "C40") (pin "2") (pinfunction "2_2") (pintype "passive"))
      (node (ref "C41") (pin "1") (pinfunction "1_1") (pintype "passive"))
      (node (ref "C60") (pin "2") (pinfunction "2_2") (pintype "passive"))
      (node (ref "Q1") (pin "D") (pinfunction "D_D") (pintype "passive"))
      (node (ref "Q2") (pin "D") (pinfunction "D_D") (pintype "passive"))
      (node (ref "Q3") (pin "D") (pinfunction "D_D") (pintype "passive"))
      (node (ref "Q4") (pin "D") (pinfunction "D_D") (pintype "passive"))
      (node (ref "Q5") (pin "D") (pinfunction "D_D") (pintype "passive"))
      (node (ref "Q6") (pin "D") (pinfunction "D_D") (pintype "passive"))
      (node (ref "U4") (pin "29") (pinfunction "PVDD1_29") (pintype "passive"))
      (node (ref "U4") (pin "53") (pinfunction "PVDD2_53") (pintype "passive"))
      (node (ref "U4") (pin "54") (pinfunction "PVDD2_54") (pintype "passive"))
    )
    (net (code "37") (name "GND") (class "Default")
      (node (ref "C24") (pin "2") (pinfunction "2_2") (pintype "passive"))
      (node (ref "C25") (pin "2") (pinfunction "2_2") (pintype "passive"))
      (node (ref "C27") (pin "2") (pinfunction "2_2") (pintype "passive"))
      (node (ref "C29") (pin "2") (pinfunction "2_2") (pintype "passive"))
      (node (ref "C32") (pin "1") (pinfunction "1_1") (pintype "passive"))
      (node (ref "C41") (pin "2") (pinfunction "2_2") (pintype "passive"))
      (node (ref "C60") (pin "1") (pinfunction "1_1") (pintype "passive"))
      (node (ref "D1") (pin "A") (pinfunction "A_A") (pintype "passive"))
      (node (ref "R15") (pin "2") (pinfunction "0_2") (pintype "passive"))
      (node (ref "R20") (pin "2") (pinfunction "0_2") (pintype "passive"))
      (node (ref "R21") (pin "2") (pinfunction "0_2") (pintype "passive"))
      (node (ref "U4") (pin "57") (pinfunction "GND_(PowerPAD)_57") (pintype "passive"))
    )
    (net (code "38") (name "GVDD") (class "Default")
      (node (ref "C32") (pin "2") (pinfunction "2_2") (pintype "passive"))
      (node (ref "U4") (pin "13") (pinfunction "GVDD_13") (pintype "passive"))
    )
    (net (code "39") (name "Net-(C27-Pad1)") (class "Default")
      (node (ref "C27") (pin "1") (pinfunction "1_1") (pintype "passive"))
      (node (ref "R14") (pin "2") (pinfunction "0_2") (pintype "passive"))
    )
    (net (code "40") (name "Net-(C28-Pad1)") (class "Default")
      (node (ref "C28") (pin "1") (pinfunction "1_1") (pintype "passive"))
      (node (ref "D1") (pin "K") (pinfunction "K_K") (pintype "passive"))
      (node (ref "L2") (pin "1") (pinfunction "1_1") (pintype "passive"))
      (node (ref "U4") (pin "50") (pinfunction "PH_50") (pintype "passive"))
      (node (ref "U4") (pin "51") (pinfunction "PH_51") (pintype "passive"))
    )
    (net (code "41") (name "Net-(Q1-PadG)") (class "Default")
      (node (ref "Q1") (pin "G") (pinfunction "G_G") (pintype "passive"))
      (node (ref "Q2") (pin "G") (pinfunction "G_G") (pintype "passive"))
      (node (ref "R17") (pin "1") (pinfunction "0_1") (pintype "passive"))
    )
    (net (code "42") (name "Net-(Q3-PadG)") (class "Default")
      (node (ref "Q3") (pin "G") (pinfunction "G_G") (pintype "passive"))
      (node (ref "Q4") (pin "G") (pinfunction "G_G") (pintype "passive"))
      (node (ref "R18") (pin "1") (pinfunction "0_1") (pintype "passive"))
    )
    (net (code "43") (name "Net-(Q5-PadG)") (class "Default")
      (node (ref "Q5") (pin "G") (pinfunction "G_G") (pintype "passive"))
      (node (ref "Q6") (pin "G") (pinfunction "G_G") (pintype "passive"))
      (node (ref "R19") (pin "1") (pinfunction "0_1") (pintype "passive"))
    )
    (net (code "44") (name "Net-(Q7-PadG)") (class "Default")
      (node (ref "Q7") (pin "G") (pinfunction "G_G") (pintype "passive"))
      (node (ref "Q8") (pin "G") (pinfunction "G_G") (pintype "passive"))
      (node (ref "R22") (pin "1") (pinfunction "0_1") (pintype "passive"))
    )
    (net (code "45") (name "Net-(Q10-PadG)") (class "Default")
      (node (ref "Q10") (pin "G") (pinfunction "G_G") (pintype "passive"))
      (node (ref "Q9") (pin "G") (pinfunction "G_G") (pintype "passive"))
      (node (ref "R23") (pin "1") (pinfunction "0_1") (pintype "passive"))
    )
    (net (code "46") (name "Net-(Q11-PadG)") (class "Default")
      (node (ref "Q11") (pin "G") (pinfunction "G_G") (pintype "passive"))
      (node (ref "Q12") (pin "G") (pinfunction "G_G") (pintype "passive"))
      (node (ref "R24") (pin "1") (pinfunction "0_1") (pintype "passive"))
    )
    (net (code "47") (name "Net-(U4-AVDD)") (class "Default")
      (node (ref "C37") (pin "2") (pinfunction "2_2") (pintype "passive"))
      (node (ref "U4") (pin "27") (pinfunction "AVDD_27") (pintype "passive"))
    )
    (net (code "48") (name "Net-(U4-BST_A)") (class "Default")
      (node (ref "C30") (pin "2") (pinfunction "2_2") (pintype "passive"))
      (node (ref "U4") (pin "48") (pinfunction "BST_A_48") (pintype "passive"))
    )
    (net (code "49") (name "Net-(U4-BST_B)") (class "Default")
      (node (ref "C31") (pin "2") (pinfunction "2_2") (pintype "passive"))
      (node (ref "U4") (pin "43") (pinfunction "BST_B_43") (pintype "passive"))
    )
    (net (code "50") (name "Net-(U4-BST_BK)") (class "Default")
      (node (ref "C28") (pin "2") (pinfunction "2_2") (pintype "passive"))
      (node (ref "U4") (pin "52") (pinfunction "BST_BK_52") (pintype "passive"))
    )
    (net (code "51") (name "Net-(U4-BST_C)") (class "Default")
      (node (ref "C34") (pin "2") (pinfunction "2_2") (pintype "passive"))
      (node (ref "U4") (pin "38") (pinfunction "BST_C_38") (pintype "passive"))
    )
    (net (code "52") (name "Net-(U4-COMP)") (class "Default")
      (node (ref "C24") (pin "1") (pinfunction "1_1") (pintype "passive"))
      (node (ref "R14") (pin "1") (pinfunction "0_1") (pintype "passive"))
      (node (ref "U4") (pin "2") (pinfunction "COMP_2") (pintype "passive"))
    )
    (net (code "53") (name "Net-(U4-CP1)") (class "Default")
      (node (ref "C33") (pin "1") (pinfunction "1_1") (pintype "passive"))
      (node (ref "U4") (pin "14") (pinfunction "CP1_14") (pintype "passive"))
    )
    (net (code "54") (name "Net-(U4-CP2)") (class "Default")
      (node (ref "C33") (pin "2") (pinfunction "2_2") (pintype "passive"))
      (node (ref "U4") (pin "15") (pinfunction "CP2_15") (pintype "passive"))
    )
    (net (code "55") (name "Net-(U4-DTC)") (class "Default")
      (node (ref "R21") (pin "1") (pinfunction "0_1") (pintype "passive"))
      (node (ref "U4") (pin "7") (pinfunction "DTC_7") (pintype "passive"))
    )
    (net (code "56") (name "Net-(U4-DVDD)") (class "Default")
      (node (ref "C35") (pin "2") (pinfunction "2_2") (pintype "passive"))
      (node (ref "U4") (pin "23") (pinfunction "DVDD_23") (pintype "passive"))
    )
    (net (code "57") (name "Net-(U4-RT_CLK)") (class "Default")
      (node (ref "R15") (pin "1") (pinfunction "0_1") (pintype "passive"))
      (node (ref "U4") (pin "1") (pinfunction "RT_CLK_1") (pintype "passive"))
    )
    (net (code "58") (name "Net-(U4-SN1)") (class "Default")
      (node (ref "C36") (pin "1") (pinfunction "1_1") (pintype "passive"))
      (node (ref "R25") (pin "2") (pinfunction "0_2") (pintype "passive"))
      (node (ref "U4") (pin "33") (pinfunction "SN1_33") (pintype "passive"))
    )
    (net (code "59") (name "Net-(U4-SN2)") (class "Default")
      (node (ref "C42") (pin "1") (pinfunction "1_1") (pintype "passive"))
      (node (ref "R30") (pin "2") (pinfunction "0_2") (pintype "passive"))
      (node (ref "U4") (pin "31") (pinfunction "SN2_31") (pintype "passive"))
    )
    (net (code "60") (name "Net-(U4-SO1)") (class "Default")
      (node (ref "R26") (pin "1") (pinfunction "0_1") (pintype "passive"))
      (node (ref "U4") (pin "25") (pinfunction "SO1_25") (pintype "passive"))
    )
    (net (code "61") (name "Net-(U4-SO2)") (class "Default")
      (node (ref "R29") (pin "1") (pinfunction "0_1") (pintype "passive"))
      (node (ref "U4") (pin "26") (pinfunction "SO2_26") (pintype "passive"))
    )
    (net (code "62") (name "Net-(U4-VSENSE)") (class "Default")
      (node (ref "R16") (pin "2") (pinfunction "0_2") (pintype "passive"))
      (node (ref "R20") (pin "1") (pinfunction "0_1") (pintype "passive"))
      (node (ref "U4") (pin "3") (pinfunction "VSENSE_3") (pintype "passive"))
    )
    (net (code "63") (name "PGND") (class "Default")
      (node (ref "C26") (pin "1") (pinfunction "1_1") (pintype "passive"))
      (node (ref "C40") (pin "1") (pinfunction "1_1") (pintype "passive"))
      (node (ref "NT2") (pin "2") (pintype "passive"))
      (node (ref "NT3") (pin "2") (pintype "passive"))
      (node (ref "Q7") (pin "S") (pinfunction "S_S") (pintype "passive"))
      (node (ref "Q8") (pin "S") (pinfunction "S_S") (pintype "passive"))
      (node (ref "R27") (pin "1") (pinfunction "0_1") (pintype "passive"))
      (node (ref "R28") (pin "1") (pinfunction "0_1") (pintype "passive"))
      (node (ref "U4") (pin "44") (pinfunction "SL_A_44") (pintype "passive"))
    )
    (net (code "64") (name "VCC") (class "Default")
      (node (ref "U4") (pin "49") (pinfunction "VDD_SPI_49") (pintype "passive"))
    )
    (net (code "65") (name "unconnected-(U4-EN_BUCK-Pad55)") (class "Default")
      (node (ref "U4") (pin "55") (pinfunction "EN_BUCK_55") (pintype "passive"))
    )
    (net (code "66") (name "unconnected-(U4-PWRGD-Pad4)") (class "Default")
      (node (ref "U4") (pin "4") (pinfunction "PWRGD_4") (pintype "passive"))
    )
    (net (code "67") (name "unconnected-(U4-SS_TR-Pad56)") (class "Default")
      (node (ref "U4") (pin "56") (pinfunction "SS_TR_56") (pintype "passive"))
    )
  )
)
